# X2C_DC_SHIELD.net
KiCad netlist of a schematic drawn in EAGLE
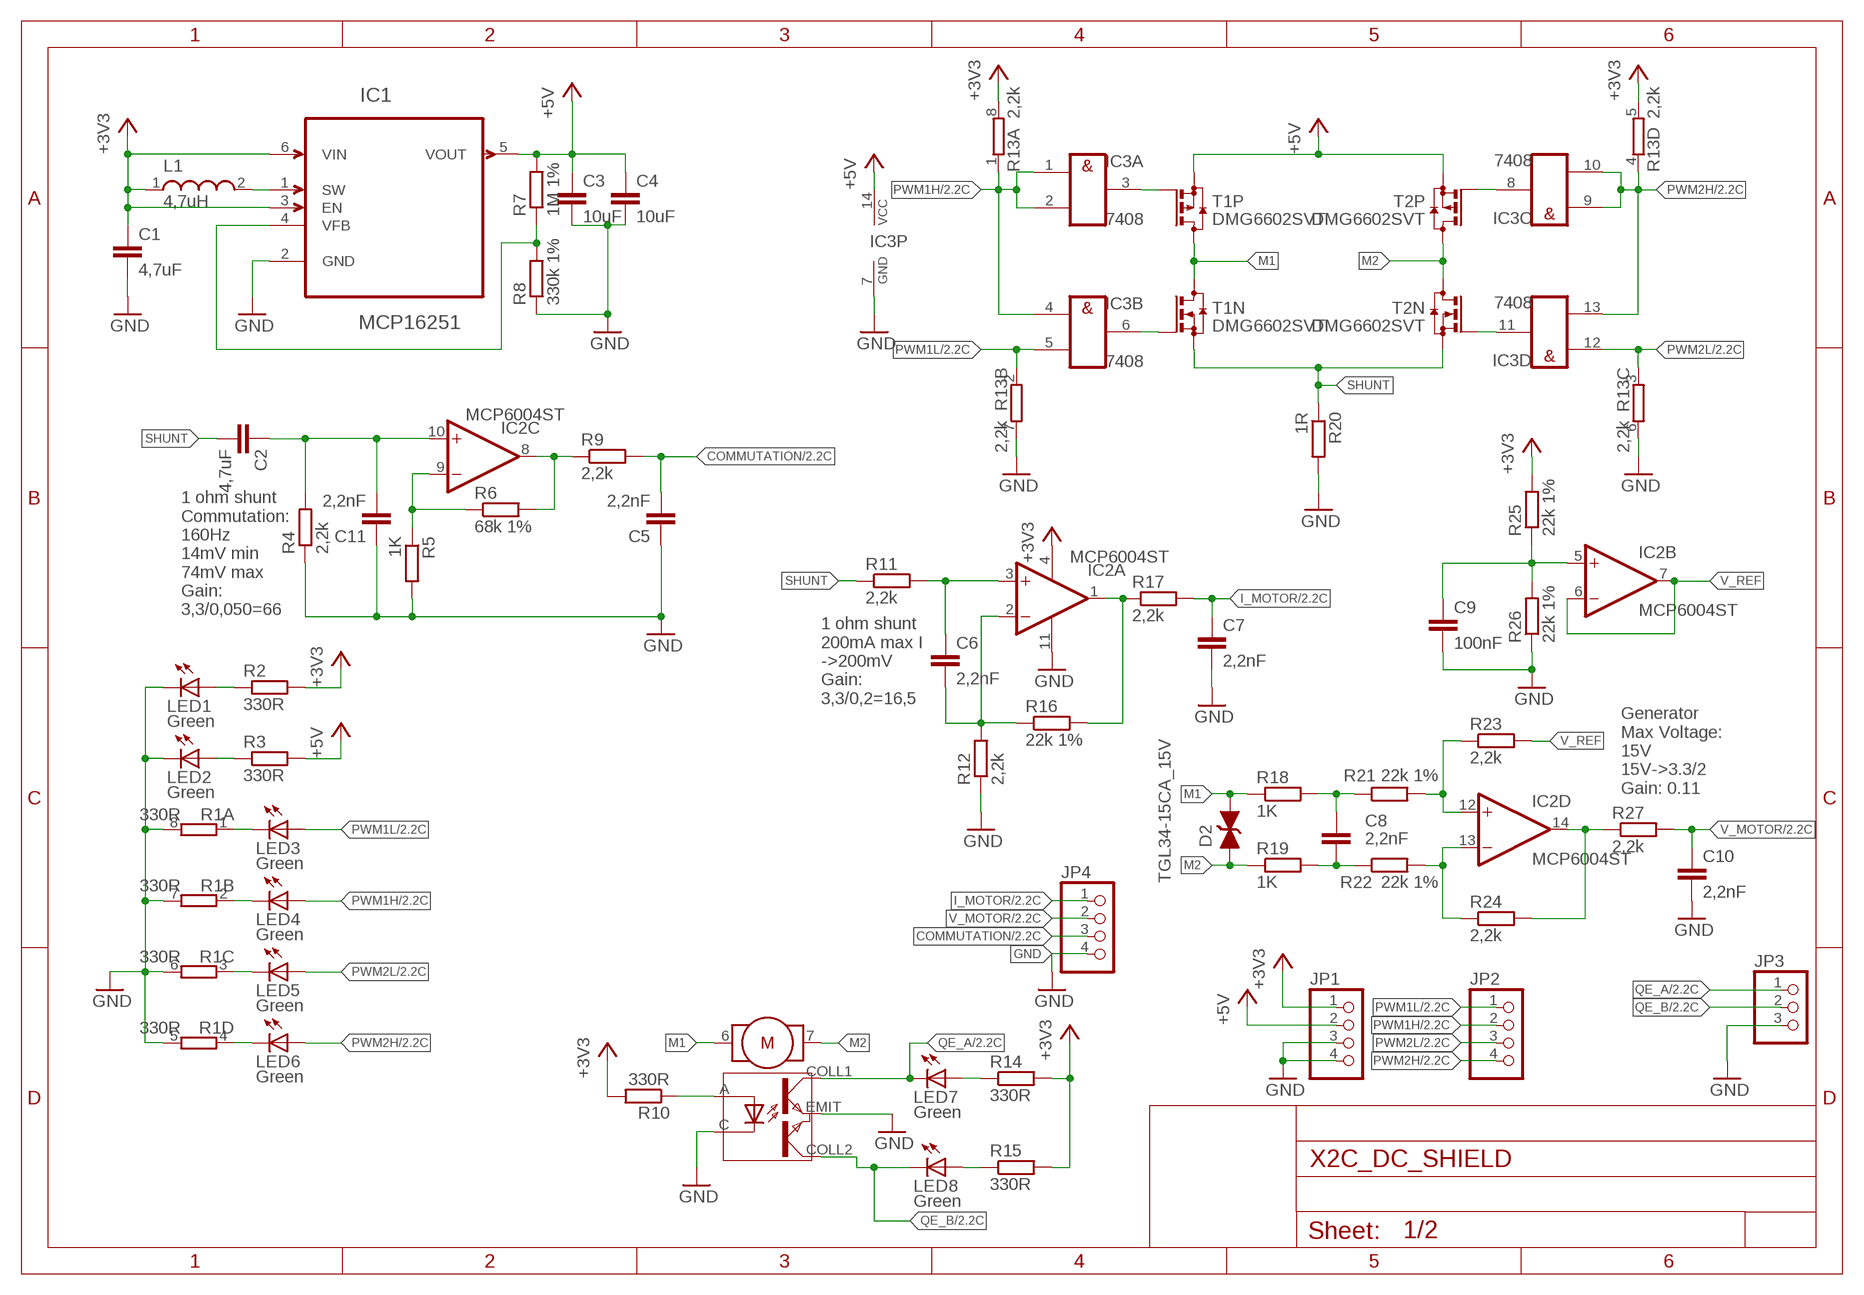
[diagram p0: schematic, sheet 1]
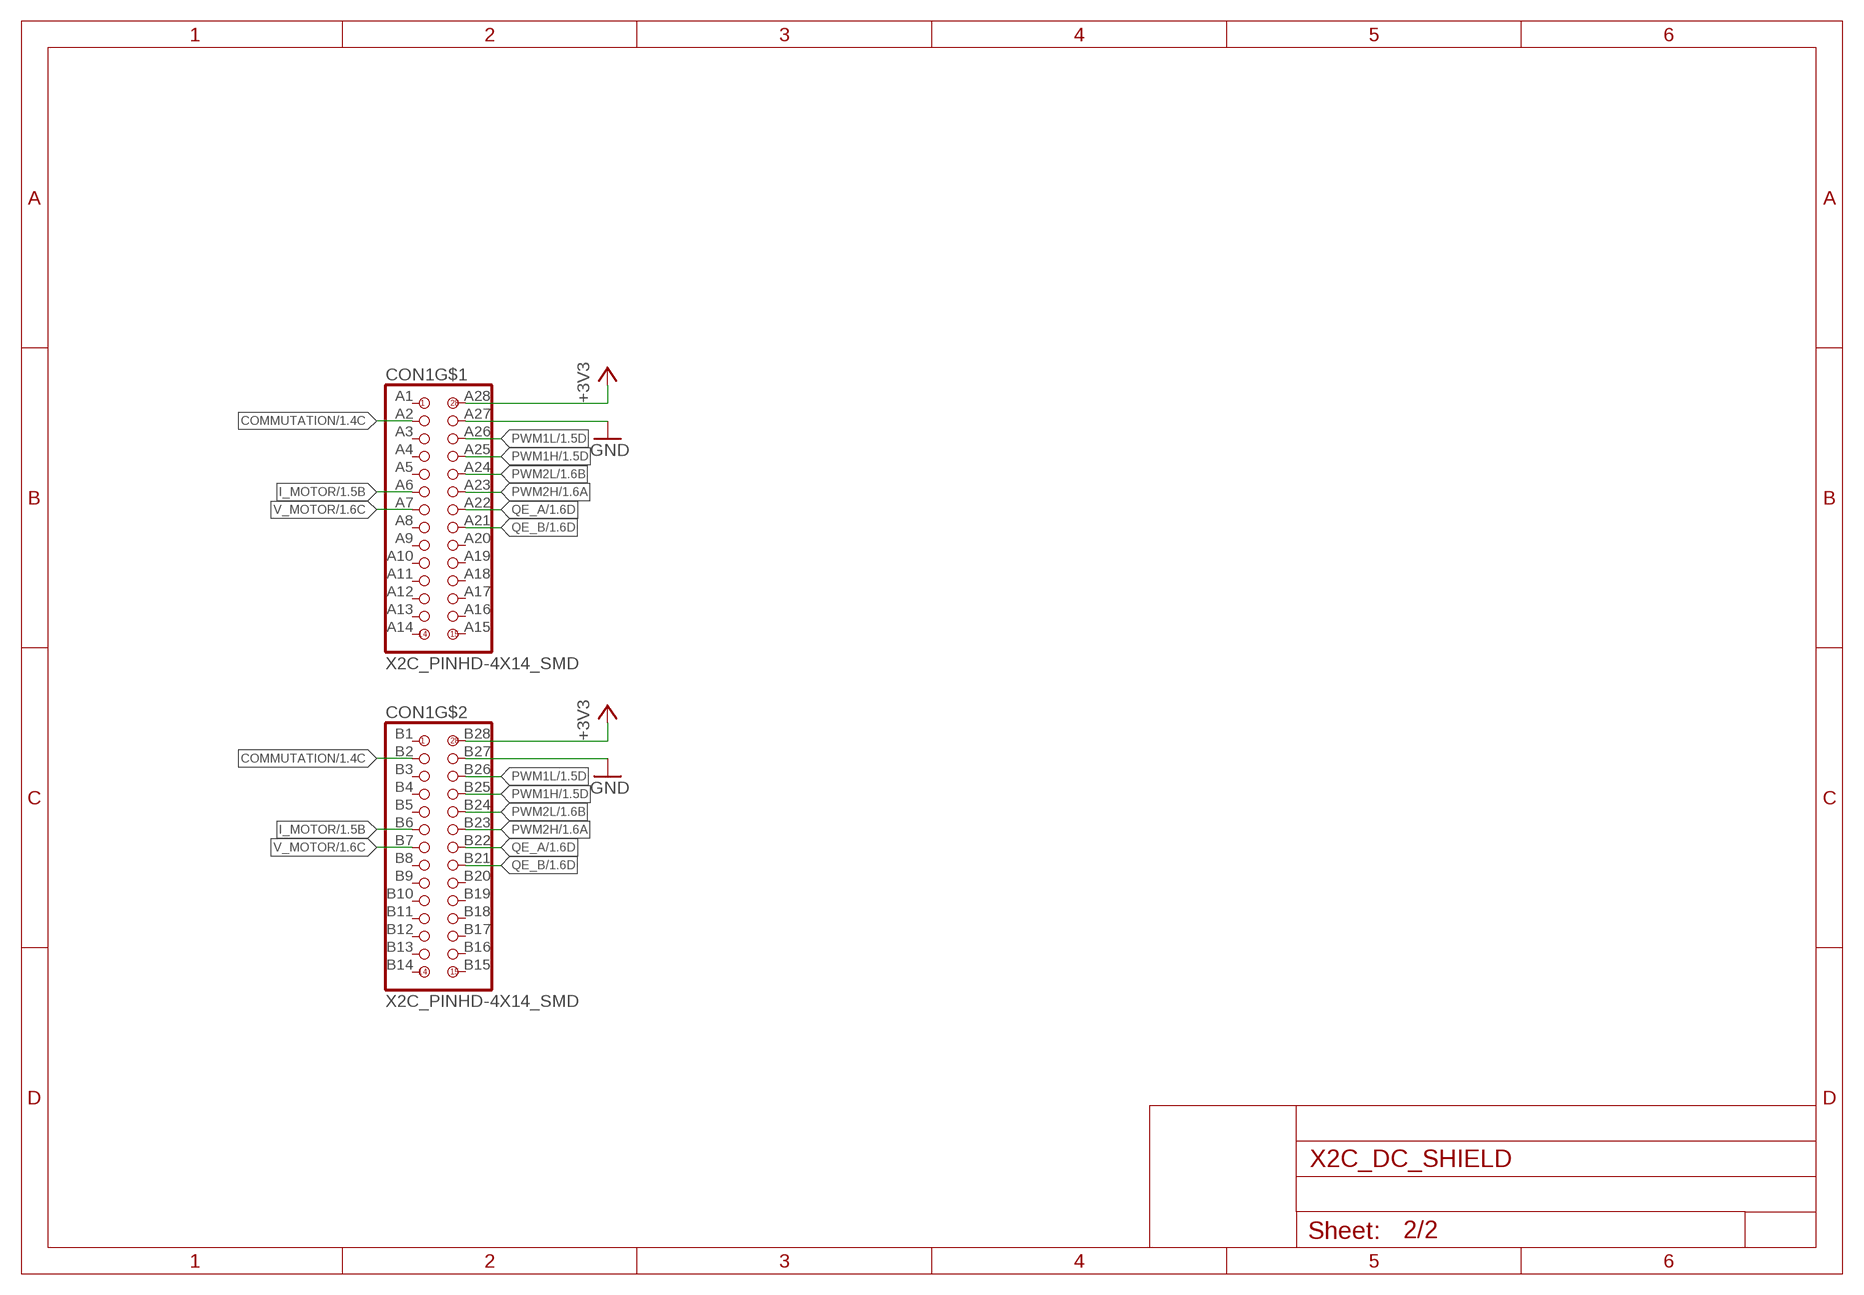
[diagram p1: schematic, sheet 2]

(export (version "E")
  (design (tool "Eeschema 10.0.6"))
  (components
    (comp (ref "CON1")
      (value "X2C_PINHD-4X14_SMD")
      (footprint "eagle-import:X2C_4X14_SMD")
      (libsource (lib "eagle-import") (part "X2C_PINHD-4X14_SMD"))
    )
    (comp (ref "C1")
      (value "4,7uF")
      (footprint "eagle-import:C0603K")
      (libsource (lib "eagle-import") (part "KANDO_KOZOS_C-EU-SMD_0603_4,7UF_16V"))
    )
    (comp (ref "C2")
      (value "4,7uF")
      (footprint "eagle-import:C0603K")
      (libsource (lib "eagle-import") (part "KANDO_KOZOS_C-EU-SMD_0603_4,7UF_16V"))
    )
    (comp (ref "C3")
      (value "10uF")
      (footprint "eagle-import:C0805K")
      (libsource (lib "eagle-import") (part "C-EU-SMD_0805_10UF_16V"))
    )
    (comp (ref "C4")
      (value "10uF")
      (footprint "eagle-import:C0805K")
      (libsource (lib "eagle-import") (part "C-EU-SMD_0805_10UF_16V"))
    )
    (comp (ref "C5")
      (value "2,2nF")
      (footprint "eagle-import:C0603K")
      (libsource (lib "eagle-import") (part "KANDO_KOZOS_C-EU-SMD_0603_2,2NF"))
    )
    (comp (ref "C6")
      (value "2,2nF")
      (footprint "eagle-import:C0603K")
      (libsource (lib "eagle-import") (part "KANDO_KOZOS_C-EU-SMD_0603_2,2NF"))
    )
    (comp (ref "C7")
      (value "2,2nF")
      (footprint "eagle-import:C0603K")
      (libsource (lib "eagle-import") (part "KANDO_KOZOS_C-EU-SMD_0603_2,2NF"))
    )
    (comp (ref "C8")
      (value "2,2nF")
      (footprint "eagle-import:C0603K")
      (libsource (lib "eagle-import") (part "KANDO_KOZOS_C-EU-SMD_0603_2,2NF"))
    )
    (comp (ref "C9")
      (value "100nF")
      (footprint "eagle-import:C0603K")
      (libsource (lib "eagle-import") (part "KANDO_KOZOS_C-EU-SMD_0603_100NF_50V"))
    )
    (comp (ref "C10")
      (value "2,2nF")
      (footprint "eagle-import:C0603K")
      (libsource (lib "eagle-import") (part "KANDO_KOZOS_C-EU-SMD_0603_2,2NF"))
    )
    (comp (ref "C11")
      (value "2,2nF")
      (footprint "eagle-import:C0603K")
      (libsource (lib "eagle-import") (part "KANDO_KOZOS_C-EU-SMD_0603_2,2NF"))
    )
    (comp (ref "D2")
      (value "TGL34-15CA_15V")
      (footprint "eagle-import:DO213AA")
      (libsource (lib "eagle-import") (part "TRANSIL_DUAL_DIODE"))
    )
    (comp (ref "IC1")
      (value "MCP16251")
      (footprint "eagle-import:SOT95P270X145-6N")
      (libsource (lib "eagle-import") (part "MCP16251"))
    )
    (comp (ref "IC2")
      (value "MCP6004ST")
      (footprint "eagle-import:TSSOP14")
      (libsource (lib "eagle-import") (part "MCP6004ST"))
    )
    (comp (ref "IC3")
      (value "7408")
      (footprint "eagle-import:TSSOP14")
      (libsource (lib "eagle-import") (part "7408"))
    )
    (comp (ref "JP1")
      (value "PINHD-1X4")
      (footprint "eagle-import:1X04")
      (libsource (lib "eagle-import") (part "PINHD-1X4"))
    )
    (comp (ref "JP2")
      (value "PINHD-1X4")
      (footprint "eagle-import:1X04")
      (libsource (lib "eagle-import") (part "PINHD-1X4"))
    )
    (comp (ref "JP3")
      (value "PINHD-1X03_2.54")
      (footprint "eagle-import:1X03")
      (libsource (lib "eagle-import") (part "PINHD-1X03_2.54"))
    )
    (comp (ref "JP4")
      (value "PINHD-1X4")
      (footprint "eagle-import:1X04")
      (libsource (lib "eagle-import") (part "PINHD-1X4"))
    )
    (comp (ref "L1")
      (value "4,7uH")
      (footprint "eagle-import:WE-TPC_3816")
      (libsource (lib "eagle-import") (part "WE-TPC_3816_4,7UH_0,9A"))
    )
    (comp (ref "LED1")
      (value "Green")
      (footprint "eagle-import:CHIPLED_0805")
      (libsource (lib "eagle-import") (part "LEDCHIPLED_0805_GREEN"))
    )
    (comp (ref "LED2")
      (value "Green")
      (footprint "eagle-import:CHIPLED_0805")
      (libsource (lib "eagle-import") (part "LEDCHIPLED_0805_GREEN"))
    )
    (comp (ref "LED3")
      (value "Green")
      (footprint "eagle-import:CHIPLED_0805")
      (libsource (lib "eagle-import") (part "LEDCHIPLED_0805_GREEN"))
    )
    (comp (ref "LED4")
      (value "Green")
      (footprint "eagle-import:CHIPLED_0805")
      (libsource (lib "eagle-import") (part "LEDCHIPLED_0805_GREEN"))
    )
    (comp (ref "LED5")
      (value "Green")
      (footprint "eagle-import:CHIPLED_0805")
      (libsource (lib "eagle-import") (part "LEDCHIPLED_0805_GREEN"))
    )
    (comp (ref "LED6")
      (value "Green")
      (footprint "eagle-import:CHIPLED_0805")
      (libsource (lib "eagle-import") (part "LEDCHIPLED_0805_GREEN"))
    )
    (comp (ref "LED7")
      (value "Green")
      (footprint "eagle-import:CHIPLED_0805")
      (libsource (lib "eagle-import") (part "LEDCHIPLED_0805_GREEN"))
    )
    (comp (ref "LED8")
      (value "Green")
      (footprint "eagle-import:CHIPLED_0805")
      (libsource (lib "eagle-import") (part "LEDCHIPLED_0805_GREEN"))
    )
    (comp (ref "MOT1")
      (value "DC_MOT")
      (footprint "eagle-import:DC_MOTOR")
      (libsource (lib "eagle-import") (part "DC_MOTOR_1"))
    )
    (comp (ref "R1")
      (value "330R")
      (footprint "eagle-import:EXBV8V_A")
      (libsource (lib "eagle-import") (part "4R-N330R"))
    )
    (comp (ref "R2")
      (value "330R")
      (footprint "eagle-import:R0603")
      (libsource (lib "eagle-import") (part "R-EU_SMDR0603_330R"))
    )
    (comp (ref "R3")
      (value "330R")
      (footprint "eagle-import:R0603")
      (libsource (lib "eagle-import") (part "R-EU_SMDR0603_330R"))
    )
    (comp (ref "R4")
      (value "2,2k")
      (footprint "eagle-import:R0603")
      (libsource (lib "eagle-import") (part "R-EU_SMDR0603_2,2K"))
    )
    (comp (ref "R5")
      (value "1K")
      (footprint "eagle-import:R0603")
      (libsource (lib "eagle-import") (part "R-EU_SMDR0603_1K_1%"))
    )
    (comp (ref "R6")
      (value "68k 1%")
      (footprint "eagle-import:R0603")
      (libsource (lib "eagle-import") (part "R-EU_SMDR0603_68K_1%"))
    )
    (comp (ref "R7")
      (value "1M 1%")
      (footprint "eagle-import:R0603")
      (libsource (lib "eagle-import") (part "R-EU_SMDR0603_1M_1%"))
    )
    (comp (ref "R8")
      (value "330k 1%")
      (footprint "eagle-import:R0603")
      (libsource (lib "eagle-import") (part "R-EU_SMDR0603_330K_1%"))
    )
    (comp (ref "R9")
      (value "2,2k")
      (footprint "eagle-import:R0603")
      (libsource (lib "eagle-import") (part "R-EU_SMDR0603_2,2K"))
    )
    (comp (ref "R10")
      (value "330R")
      (footprint "eagle-import:R0603")
      (libsource (lib "eagle-import") (part "R-EU_SMDR0603_330R"))
    )
    (comp (ref "R11")
      (value "2,2k")
      (footprint "eagle-import:R0603")
      (libsource (lib "eagle-import") (part "R-EU_SMDR0603_2,2K"))
    )
    (comp (ref "R12")
      (value "2,2k")
      (footprint "eagle-import:R0603")
      (libsource (lib "eagle-import") (part "R-EU_SMDR0603_2,2K"))
    )
    (comp (ref "R13")
      (value "2,2k")
      (footprint "eagle-import:EXBV8V_A")
      (libsource (lib "eagle-import") (part "4R-N2,2K"))
    )
    (comp (ref "R14")
      (value "330R")
      (footprint "eagle-import:R0603")
      (libsource (lib "eagle-import") (part "R-EU_SMDR0603_330R"))
    )
    (comp (ref "R15")
      (value "330R")
      (footprint "eagle-import:R0603")
      (libsource (lib "eagle-import") (part "R-EU_SMDR0603_330R"))
    )
    (comp (ref "R16")
      (value "22k 1%")
      (footprint "eagle-import:R0603")
      (libsource (lib "eagle-import") (part "R-EU_SMDR0603_22K_1%"))
    )
    (comp (ref "R17")
      (value "2,2k")
      (footprint "eagle-import:R0603")
      (libsource (lib "eagle-import") (part "R-EU_SMDR0603_2,2K"))
    )
    (comp (ref "R18")
      (value "1K")
      (footprint "eagle-import:R0603")
      (libsource (lib "eagle-import") (part "R-EU_SMDR0603_1K_1%"))
    )
    (comp (ref "R19")
      (value "1K")
      (footprint "eagle-import:R0603")
      (libsource (lib "eagle-import") (part "R-EU_SMDR0603_1K_1%"))
    )
    (comp (ref "R20")
      (value "1R")
      (footprint "eagle-import:R0805")
      (libsource (lib "eagle-import") (part "R-EU_SMDR0805_1R_1%"))
    )
    (comp (ref "R21")
      (value "22k 1%")
      (footprint "eagle-import:R0603")
      (libsource (lib "eagle-import") (part "R-EU_SMDR0603_22K_1%"))
    )
    (comp (ref "R22")
      (value "22k 1%")
      (footprint "eagle-import:R0603")
      (libsource (lib "eagle-import") (part "R-EU_SMDR0603_22K_1%"))
    )
    (comp (ref "R23")
      (value "2,2k")
      (footprint "eagle-import:R0603")
      (libsource (lib "eagle-import") (part "R-EU_SMDR0603_2,2K"))
    )
    (comp (ref "R24")
      (value "2,2k")
      (footprint "eagle-import:R0603")
      (libsource (lib "eagle-import") (part "R-EU_SMDR0603_2,2K"))
    )
    (comp (ref "R25")
      (value "22k 1%")
      (footprint "eagle-import:R0603")
      (libsource (lib "eagle-import") (part "R-EU_SMDR0603_22K_1%"))
    )
    (comp (ref "R26")
      (value "22k 1%")
      (footprint "eagle-import:R0603")
      (libsource (lib "eagle-import") (part "R-EU_SMDR0603_22K_1%"))
    )
    (comp (ref "R27")
      (value "2,2k")
      (footprint "eagle-import:R0603")
      (libsource (lib "eagle-import") (part "R-EU_SMDR0603_2,2K"))
    )
    (comp (ref "T1")
      (value "DMG6602SVT")
      (footprint "eagle-import:TSOT23-6")
      (libsource (lib "eagle-import") (part "DMG6602SVT"))
    )
    (comp (ref "T2")
      (value "DMG6602SVT")
      (footprint "eagle-import:TSOT23-6")
      (libsource (lib "eagle-import") (part "DMG6602SVT"))
    )
  )
  (nets
    (net (code "1") (name "+3V3") (class "Default")
      (node (ref "C1") (pin "1") (pinfunction "1_1") (pintype "passive"))
      (node (ref "CON1") (pin "A28") (pinfunction "A28_A28") (pintype "passive"))
      (node (ref "CON1") (pin "B28") (pinfunction "A28_B28") (pintype "passive"))
      (node (ref "IC1") (pin "3") (pinfunction "EN_3") (pintype "input"))
      (node (ref "IC1") (pin "6") (pinfunction "VIN_6") (pintype "input"))
      (node (ref "IC2") (pin "4") (pinfunction "V+_4") (pintype "power_in"))
      (node (ref "JP1") (pin "1") (pinfunction "1_1") (pintype "passive"))
      (node (ref "L1") (pin "1") (pinfunction "1_1") (pintype "passive"))
      (node (ref "R10") (pin "2") (pinfunction "2_2") (pintype "passive"))
      (node (ref "R13") (pin "5") (pinfunction "2_5") (pintype "passive"))
      (node (ref "R13") (pin "8") (pinfunction "2_8") (pintype "passive"))
      (node (ref "R14") (pin "2") (pinfunction "2_2") (pintype "passive"))
      (node (ref "R15") (pin "2") (pinfunction "2_2") (pintype "passive"))
      (node (ref "R2") (pin "2") (pinfunction "2_2") (pintype "passive"))
      (node (ref "R25") (pin "2") (pinfunction "2_2") (pintype "passive"))
    )
    (net (code "2") (name "+5V") (class "Default")
      (node (ref "C3") (pin "1") (pinfunction "1_1") (pintype "passive"))
      (node (ref "C4") (pin "1") (pinfunction "1_1") (pintype "passive"))
      (node (ref "IC1") (pin "5") (pinfunction "VOUT_5") (pintype "output"))
      (node (ref "IC3") (pin "14") (pinfunction "VCC_14") (pintype "power_in"))
      (node (ref "JP1") (pin "2") (pinfunction "2_2") (pintype "passive"))
      (node (ref "R3") (pin "2") (pinfunction "2_2") (pintype "passive"))
      (node (ref "R7") (pin "2") (pinfunction "2_2") (pintype "passive"))
      (node (ref "T1") (pin "2") (pinfunction "S_2") (pintype "passive"))
      (node (ref "T2") (pin "2") (pinfunction "S_2") (pintype "passive"))
    )
    (net (code "3") (name "COMMUTATION") (class "Default")
      (node (ref "C5") (pin "2") (pinfunction "2_2") (pintype "passive"))
      (node (ref "CON1") (pin "A2") (pinfunction "A2_A2") (pintype "passive"))
      (node (ref "CON1") (pin "B2") (pinfunction "A2_B2") (pintype "passive"))
      (node (ref "JP4") (pin "3") (pinfunction "3_3") (pintype "passive"))
      (node (ref "R9") (pin "2") (pinfunction "2_2") (pintype "passive"))
    )
    (net (code "4") (name "GND") (class "Default")
      (node (ref "C1") (pin "2") (pinfunction "2_2") (pintype "passive"))
      (node (ref "C10") (pin "2") (pinfunction "2_2") (pintype "passive"))
      (node (ref "C11") (pin "1") (pinfunction "1_1") (pintype "passive"))
      (node (ref "C3") (pin "2") (pinfunction "2_2") (pintype "passive"))
      (node (ref "C4") (pin "2") (pinfunction "2_2") (pintype "passive"))
      (node (ref "C5") (pin "1") (pinfunction "1_1") (pintype "passive"))
      (node (ref "C7") (pin "2") (pinfunction "2_2") (pintype "passive"))
      (node (ref "C9") (pin "2") (pinfunction "2_2") (pintype "passive"))
      (node (ref "CON1") (pin "A27") (pinfunction "A27_A27") (pintype "passive"))
      (node (ref "CON1") (pin "B27") (pinfunction "A27_B27") (pintype "passive"))
      (node (ref "IC1") (pin "2") (pinfunction "GND_2") (pintype "passive"))
      (node (ref "IC2") (pin "11") (pinfunction "V-_11") (pintype "power_in"))
      (node (ref "IC3") (pin "7") (pinfunction "GND_7") (pintype "power_in"))
      (node (ref "JP1") (pin "3") (pinfunction "3_3") (pintype "passive"))
      (node (ref "JP1") (pin "4") (pinfunction "4_4") (pintype "passive"))
      (node (ref "JP3") (pin "3") (pinfunction "3_3") (pintype "passive"))
      (node (ref "JP4") (pin "4") (pinfunction "4_4") (pintype "passive"))
      (node (ref "LED1") (pin "C") (pinfunction "C_C") (pintype "passive"))
      (node (ref "LED2") (pin "C") (pinfunction "C_C") (pintype "passive"))
      (node (ref "MOT1") (pin "C") (pinfunction "C_C") (pintype "passive"))
      (node (ref "MOT1") (pin "EMIT") (pinfunction "EMIT_EMIT") (pintype "passive"))
      (node (ref "R1") (pin "5") (pinfunction "2_5") (pintype "passive"))
      (node (ref "R1") (pin "6") (pinfunction "2_6") (pintype "passive"))
      (node (ref "R1") (pin "7") (pinfunction "2_7") (pintype "passive"))
      (node (ref "R1") (pin "8") (pinfunction "2_8") (pintype "passive"))
      (node (ref "R12") (pin "1") (pinfunction "1_1") (pintype "passive"))
      (node (ref "R13") (pin "6") (pinfunction "2_6") (pintype "passive"))
      (node (ref "R13") (pin "7") (pinfunction "2_7") (pintype "passive"))
      (node (ref "R20") (pin "2") (pinfunction "2_2") (pintype "passive"))
      (node (ref "R26") (pin "1") (pinfunction "1_1") (pintype "passive"))
      (node (ref "R4") (pin "1") (pinfunction "1_1") (pintype "passive"))
      (node (ref "R5") (pin "2") (pinfunction "2_2") (pintype "passive"))
      (node (ref "R8") (pin "1") (pinfunction "1_1") (pintype "passive"))
    )
    (net (code "5") (name "I_MOTOR") (class "Default")
      (node (ref "C7") (pin "1") (pinfunction "1_1") (pintype "passive"))
      (node (ref "CON1") (pin "A6") (pinfunction "A6_A6") (pintype "passive"))
      (node (ref "CON1") (pin "B6") (pinfunction "A6_B6") (pintype "passive"))
      (node (ref "JP4") (pin "1") (pinfunction "1_1") (pintype "passive"))
      (node (ref "R17") (pin "2") (pinfunction "2_2") (pintype "passive"))
    )
    (net (code "6") (name "M1") (class "Default")
      (node (ref "D2") (pin "C") (pinfunction "P$2_C") (pintype "bidirectional"))
      (node (ref "MOT1") (pin "6") (pinfunction "MOT1_6") (pintype "passive"))
      (node (ref "R18") (pin "1") (pinfunction "1_1") (pintype "passive"))
      (node (ref "T1") (pin "4") (pinfunction "D_4") (pintype "passive"))
      (node (ref "T1") (pin "6") (pinfunction "D_6") (pintype "passive"))
    )
    (net (code "7") (name "M2") (class "Default")
      (node (ref "D2") (pin "A") (pinfunction "P$1_A") (pintype "bidirectional"))
      (node (ref "MOT1") (pin "7") (pinfunction "MOT2_7") (pintype "passive"))
      (node (ref "R19") (pin "1") (pinfunction "1_1") (pintype "passive"))
      (node (ref "T2") (pin "4") (pinfunction "D_4") (pintype "passive"))
      (node (ref "T2") (pin "6") (pinfunction "D_6") (pintype "passive"))
    )
    (net (code "8") (name "Net-(C8-Pad1)") (class "Default")
      (node (ref "C8") (pin "1") (pinfunction "1_1") (pintype "passive"))
      (node (ref "R18") (pin "2") (pinfunction "2_2") (pintype "passive"))
      (node (ref "R21") (pin "1") (pinfunction "1_1") (pintype "passive"))
    )
    (net (code "9") (name "Net-(C8-Pad2)") (class "Default")
      (node (ref "C8") (pin "2") (pinfunction "2_2") (pintype "passive"))
      (node (ref "R19") (pin "2") (pinfunction "2_2") (pintype "passive"))
      (node (ref "R22") (pin "1") (pinfunction "1_1") (pintype "passive"))
    )
    (net (code "10") (name "Net-(IC1-SW)") (class "Default")
      (node (ref "IC1") (pin "1") (pinfunction "SW_1") (pintype "input"))
      (node (ref "L1") (pin "2") (pinfunction "2_2") (pintype "passive"))
    )
    (net (code "11") (name "Net-(IC1-VFB)") (class "Default")
      (node (ref "IC1") (pin "4") (pinfunction "VFB_4") (pintype "input"))
      (node (ref "R7") (pin "1") (pinfunction "1_1") (pintype "passive"))
      (node (ref "R8") (pin "2") (pinfunction "2_2") (pintype "passive"))
    )
    (net (code "12") (name "Net-(IC2A-+IN)") (class "Default")
      (node (ref "C6") (pin "1") (pinfunction "1_1") (pintype "passive"))
      (node (ref "IC2") (pin "3") (pinfunction "+IN_3") (pintype "input"))
      (node (ref "R11") (pin "2") (pinfunction "2_2") (pintype "passive"))
    )
    (net (code "13") (name "Net-(IC2A--IN)") (class "Default")
      (node (ref "C6") (pin "2") (pinfunction "2_2") (pintype "passive"))
      (node (ref "IC2") (pin "2") (pinfunction "-IN_2") (pintype "input"))
      (node (ref "R12") (pin "2") (pinfunction "2_2") (pintype "passive"))
      (node (ref "R16") (pin "1") (pinfunction "1_1") (pintype "passive"))
    )
    (net (code "14") (name "Net-(IC2A-OUT)") (class "Default")
      (node (ref "IC2") (pin "1") (pinfunction "OUT_1") (pintype "output"))
      (node (ref "R16") (pin "2") (pinfunction "2_2") (pintype "passive"))
      (node (ref "R17") (pin "1") (pinfunction "1_1") (pintype "passive"))
    )
    (net (code "15") (name "Net-(IC2B-+IN)") (class "Default")
      (node (ref "C9") (pin "1") (pinfunction "1_1") (pintype "passive"))
      (node (ref "IC2") (pin "5") (pinfunction "+IN_5") (pintype "input"))
      (node (ref "R25") (pin "1") (pinfunction "1_1") (pintype "passive"))
      (node (ref "R26") (pin "2") (pinfunction "2_2") (pintype "passive"))
    )
    (net (code "16") (name "Net-(IC2C-+IN)") (class "Default")
      (node (ref "C11") (pin "2") (pinfunction "2_2") (pintype "passive"))
      (node (ref "C2") (pin "1") (pinfunction "1_1") (pintype "passive"))
      (node (ref "IC2") (pin "10") (pinfunction "+IN_10") (pintype "input"))
      (node (ref "R4") (pin "2") (pinfunction "2_2") (pintype "passive"))
    )
    (net (code "17") (name "Net-(IC2C--IN)") (class "Default")
      (node (ref "IC2") (pin "9") (pinfunction "-IN_9") (pintype "input"))
      (node (ref "R5") (pin "1") (pinfunction "1_1") (pintype "passive"))
      (node (ref "R6") (pin "1") (pinfunction "1_1") (pintype "passive"))
    )
    (net (code "18") (name "Net-(IC2C-OUT)") (class "Default")
      (node (ref "IC2") (pin "8") (pinfunction "OUT_8") (pintype "output"))
      (node (ref "R6") (pin "2") (pinfunction "2_2") (pintype "passive"))
      (node (ref "R9") (pin "1") (pinfunction "1_1") (pintype "passive"))
    )
    (net (code "19") (name "Net-(IC2D-+IN)") (class "Default")
      (node (ref "IC2") (pin "12") (pinfunction "+IN_12") (pintype "input"))
      (node (ref "R21") (pin "2") (pinfunction "2_2") (pintype "passive"))
      (node (ref "R23") (pin "1") (pinfunction "1_1") (pintype "passive"))
    )
    (net (code "20") (name "Net-(IC2D--IN)") (class "Default")
      (node (ref "IC2") (pin "13") (pinfunction "-IN_13") (pintype "input"))
      (node (ref "R22") (pin "2") (pinfunction "2_2") (pintype "passive"))
      (node (ref "R24") (pin "1") (pinfunction "1_1") (pintype "passive"))
    )
    (net (code "21") (name "Net-(IC2D-OUT)") (class "Default")
      (node (ref "IC2") (pin "14") (pinfunction "OUT_14") (pintype "output"))
      (node (ref "R24") (pin "2") (pinfunction "2_2") (pintype "passive"))
      (node (ref "R27") (pin "1") (pinfunction "1_1") (pintype "passive"))
    )
    (net (code "22") (name "Net-(IC3A-O)") (class "Default")
      (node (ref "IC3") (pin "3") (pinfunction "O_3") (pintype "output"))
      (node (ref "T1") (pin "3") (pinfunction "G_3") (pintype "passive"))
    )
    (net (code "23") (name "Net-(IC3B-O)") (class "Default")
      (node (ref "IC3") (pin "6") (pinfunction "O_6") (pintype "output"))
      (node (ref "T1") (pin "1") (pinfunction "G_1") (pintype "passive"))
    )
    (net (code "24") (name "Net-(IC3C-O)") (class "Default")
      (node (ref "IC3") (pin "8") (pinfunction "O_8") (pintype "output"))
      (node (ref "T2") (pin "3") (pinfunction "G_3") (pintype "passive"))
    )
    (net (code "25") (name "Net-(IC3D-O)") (class "Default")
      (node (ref "IC3") (pin "11") (pinfunction "O_11") (pintype "output"))
      (node (ref "T2") (pin "1") (pinfunction "G_1") (pintype "passive"))
    )
    (net (code "26") (name "Net-(LED1-PadA)") (class "Default")
      (node (ref "LED1") (pin "A") (pinfunction "A_A") (pintype "passive"))
      (node (ref "R2") (pin "1") (pinfunction "1_1") (pintype "passive"))
    )
    (net (code "27") (name "Net-(LED2-PadA)") (class "Default")
      (node (ref "LED2") (pin "A") (pinfunction "A_A") (pintype "passive"))
      (node (ref "R3") (pin "1") (pinfunction "1_1") (pintype "passive"))
    )
    (net (code "28") (name "Net-(LED3-PadC)") (class "Default")
      (node (ref "LED3") (pin "C") (pinfunction "C_C") (pintype "passive"))
      (node (ref "R1") (pin "1") (pinfunction "1_1") (pintype "passive"))
    )
    (net (code "29") (name "Net-(LED7-PadA)") (class "Default")
      (node (ref "LED7") (pin "A") (pinfunction "A_A") (pintype "passive"))
      (node (ref "R14") (pin "1") (pinfunction "1_1") (pintype "passive"))
    )
    (net (code "30") (name "Net-(LED8-PadA)") (class "Default")
      (node (ref "LED8") (pin "A") (pinfunction "A_A") (pintype "passive"))
      (node (ref "R15") (pin "1") (pinfunction "1_1") (pintype "passive"))
    )
    (net (code "31") (name "Net-(MOT1-PadA)") (class "Default")
      (node (ref "MOT1") (pin "A") (pinfunction "A_A") (pintype "passive"))
      (node (ref "R10") (pin "1") (pinfunction "1_1") (pintype "passive"))
    )
    (net (code "32") (name "Net-(R1B-1)") (class "Default")
      (node (ref "LED4") (pin "C") (pinfunction "C_C") (pintype "passive"))
      (node (ref "R1") (pin "2") (pinfunction "1_2") (pintype "passive"))
    )
    (net (code "33") (name "Net-(R1C-1)") (class "Default")
      (node (ref "LED5") (pin "C") (pinfunction "C_C") (pintype "passive"))
      (node (ref "R1") (pin "3") (pinfunction "1_3") (pintype "passive"))
    )
    (net (code "34") (name "Net-(R1D-1)") (class "Default")
      (node (ref "LED6") (pin "C") (pinfunction "C_C") (pintype "passive"))
      (node (ref "R1") (pin "4") (pinfunction "1_4") (pintype "passive"))
    )
    (net (code "35") (name "PWM1H") (class "Default")
      (node (ref "CON1") (pin "A25") (pinfunction "A25_A25") (pintype "passive"))
      (node (ref "CON1") (pin "B25") (pinfunction "A25_B25") (pintype "passive"))
      (node (ref "IC3") (pin "1") (pinfunction "I0_1") (pintype "input"))
      (node (ref "IC3") (pin "2") (pinfunction "I1_2") (pintype "input"))
      (node (ref "IC3") (pin "4") (pinfunction "I0_4") (pintype "input"))
      (node (ref "JP2") (pin "2") (pinfunction "2_2") (pintype "passive"))
      (node (ref "LED4") (pin "A") (pinfunction "A_A") (pintype "passive"))
      (node (ref "R13") (pin "1") (pinfunction "1_1") (pintype "passive"))
    )
    (net (code "36") (name "PWM1L") (class "Default")
      (node (ref "CON1") (pin "A26") (pinfunction "A26_A26") (pintype "passive"))
      (node (ref "CON1") (pin "B26") (pinfunction "A26_B26") (pintype "passive"))
      (node (ref "IC3") (pin "5") (pinfunction "I1_5") (pintype "input"))
      (node (ref "JP2") (pin "1") (pinfunction "1_1") (pintype "passive"))
      (node (ref "LED3") (pin "A") (pinfunction "A_A") (pintype "passive"))
      (node (ref "R13") (pin "2") (pinfunction "1_2") (pintype "passive"))
    )
    (net (code "37") (name "PWM2H") (class "Default")
      (node (ref "CON1") (pin "A23") (pinfunction "A23_A23") (pintype "passive"))
      (node (ref "CON1") (pin "B23") (pinfunction "A23_B23") (pintype "passive"))
      (node (ref "IC3") (pin "10") (pinfunction "I1_10") (pintype "input"))
      (node (ref "IC3") (pin "13") (pinfunction "I1_13") (pintype "input"))
      (node (ref "IC3") (pin "9") (pinfunction "I0_9") (pintype "input"))
      (node (ref "JP2") (pin "4") (pinfunction "4_4") (pintype "passive"))
      (node (ref "LED6") (pin "A") (pinfunction "A_A") (pintype "passive"))
      (node (ref "R13") (pin "4") (pinfunction "1_4") (pintype "passive"))
    )
    (net (code "38") (name "PWM2L") (class "Default")
      (node (ref "CON1") (pin "A24") (pinfunction "A24_A24") (pintype "passive"))
      (node (ref "CON1") (pin "B24") (pinfunction "A24_B24") (pintype "passive"))
      (node (ref "IC3") (pin "12") (pinfunction "I0_12") (pintype "input"))
      (node (ref "JP2") (pin "3") (pinfunction "3_3") (pintype "passive"))
      (node (ref "LED5") (pin "A") (pinfunction "A_A") (pintype "passive"))
      (node (ref "R13") (pin "3") (pinfunction "1_3") (pintype "passive"))
    )
    (net (code "39") (name "QE_A") (class "Default")
      (node (ref "CON1") (pin "A22") (pinfunction "A22_A22") (pintype "passive"))
      (node (ref "CON1") (pin "B22") (pinfunction "A22_B22") (pintype "passive"))
      (node (ref "JP3") (pin "1") (pinfunction "1_1") (pintype "passive"))
      (node (ref "LED7") (pin "C") (pinfunction "C_C") (pintype "passive"))
      (node (ref "MOT1") (pin "COLL1") (pinfunction "COL1_COLL1") (pintype "passive"))
    )
    (net (code "40") (name "QE_B") (class "Default")
      (node (ref "CON1") (pin "A21") (pinfunction "A21_A21") (pintype "passive"))
      (node (ref "CON1") (pin "B21") (pinfunction "A21_B21") (pintype "passive"))
      (node (ref "JP3") (pin "2") (pinfunction "2_2") (pintype "passive"))
      (node (ref "LED8") (pin "C") (pinfunction "C_C") (pintype "passive"))
      (node (ref "MOT1") (pin "COLL2") (pinfunction "COL2_COLL2") (pintype "passive"))
    )
    (net (code "41") (name "SHUNT") (class "Default")
      (node (ref "C2") (pin "2") (pinfunction "2_2") (pintype "passive"))
      (node (ref "R11") (pin "1") (pinfunction "1_1") (pintype "passive"))
      (node (ref "R20") (pin "1") (pinfunction "1_1") (pintype "passive"))
      (node (ref "T1") (pin "5") (pinfunction "S_5") (pintype "passive"))
      (node (ref "T2") (pin "5") (pinfunction "S_5") (pintype "passive"))
    )
    (net (code "42") (name "V_MOTOR") (class "Default")
      (node (ref "C10") (pin "1") (pinfunction "1_1") (pintype "passive"))
      (node (ref "CON1") (pin "A7") (pinfunction "A7_A7") (pintype "passive"))
      (node (ref "CON1") (pin "B7") (pinfunction "A7_B7") (pintype "passive"))
      (node (ref "JP4") (pin "2") (pinfunction "2_2") (pintype "passive"))
      (node (ref "R27") (pin "2") (pinfunction "2_2") (pintype "passive"))
    )
    (net (code "43") (name "V_REF") (class "Default")
      (node (ref "IC2") (pin "6") (pinfunction "-IN_6") (pintype "input"))
      (node (ref "IC2") (pin "7") (pinfunction "OUT_7") (pintype "output"))
      (node (ref "R23") (pin "2") (pinfunction "2_2") (pintype "passive"))
    )
    (net (code "44") (name "unconnected-(CON1-PadA1)") (class "Default")
      (node (ref "CON1") (pin "A1") (pinfunction "A1_A1") (pintype "passive"))
    )
    (net (code "45") (name "unconnected-(CON1-PadA3)") (class "Default")
      (node (ref "CON1") (pin "A3") (pinfunction "A3_A3") (pintype "passive"))
    )
    (net (code "46") (name "unconnected-(CON1-PadA4)") (class "Default")
      (node (ref "CON1") (pin "A4") (pinfunction "A4_A4") (pintype "passive"))
    )
    (net (code "47") (name "unconnected-(CON1-PadA5)") (class "Default")
      (node (ref "CON1") (pin "A5") (pinfunction "A5_A5") (pintype "passive"))
    )
    (net (code "48") (name "unconnected-(CON1-PadA8)") (class "Default")
      (node (ref "CON1") (pin "A8") (pinfunction "A8_A8") (pintype "passive"))
    )
    (net (code "49") (name "unconnected-(CON1-PadA9)") (class "Default")
      (node (ref "CON1") (pin "A9") (pinfunction "A9_A9") (pintype "passive"))
    )
    (net (code "50") (name "unconnected-(CON1-PadA10)") (class "Default")
      (node (ref "CON1") (pin "A10") (pinfunction "A10_A10") (pintype "passive"))
    )
    (net (code "51") (name "unconnected-(CON1-PadA11)") (class "Default")
      (node (ref "CON1") (pin "A11") (pinfunction "A11_A11") (pintype "passive"))
    )
    (net (code "52") (name "unconnected-(CON1-PadA12)") (class "Default")
      (node (ref "CON1") (pin "A12") (pinfunction "A12_A12") (pintype "passive"))
    )
    (net (code "53") (name "unconnected-(CON1-PadA13)") (class "Default")
      (node (ref "CON1") (pin "A13") (pinfunction "A13_A13") (pintype "passive"))
    )
    (net (code "54") (name "unconnected-(CON1-PadA14)") (class "Default")
      (node (ref "CON1") (pin "A14") (pinfunction "A14_A14") (pintype "passive"))
    )
    (net (code "55") (name "unconnected-(CON1-PadA15)") (class "Default")
      (node (ref "CON1") (pin "A15") (pinfunction "A15_A15") (pintype "passive"))
    )
    (net (code "56") (name "unconnected-(CON1-PadA16)") (class "Default")
      (node (ref "CON1") (pin "A16") (pinfunction "A16_A16") (pintype "passive"))
    )
    (net (code "57") (name "unconnected-(CON1-PadA17)") (class "Default")
      (node (ref "CON1") (pin "A17") (pinfunction "A17_A17") (pintype "passive"))
    )
    (net (code "58") (name "unconnected-(CON1-PadA18)") (class "Default")
      (node (ref "CON1") (pin "A18") (pinfunction "A18_A18") (pintype "passive"))
    )
    (net (code "59") (name "unconnected-(CON1-PadA19)") (class "Default")
      (node (ref "CON1") (pin "A19") (pinfunction "A19_A19") (pintype "passive"))
    )
    (net (code "60") (name "unconnected-(CON1-PadA20)") (class "Default")
      (node (ref "CON1") (pin "A20") (pinfunction "A20_A20") (pintype "passive"))
    )
    (net (code "61") (name "unconnected-(CON1B-A1-PadB1)") (class "Default")
      (node (ref "CON1") (pin "B1") (pinfunction "A1_B1") (pintype "passive"))
    )
    (net (code "62") (name "unconnected-(CON1B-A3-PadB3)") (class "Default")
      (node (ref "CON1") (pin "B3") (pinfunction "A3_B3") (pintype "passive"))
    )
    (net (code "63") (name "unconnected-(CON1B-A4-PadB4)") (class "Default")
      (node (ref "CON1") (pin "B4") (pinfunction "A4_B4") (pintype "passive"))
    )
    (net (code "64") (name "unconnected-(CON1B-A5-PadB5)") (class "Default")
      (node (ref "CON1") (pin "B5") (pinfunction "A5_B5") (pintype "passive"))
    )
    (net (code "65") (name "unconnected-(CON1B-A8-PadB8)") (class "Default")
      (node (ref "CON1") (pin "B8") (pinfunction "A8_B8") (pintype "passive"))
    )
    (net (code "66") (name "unconnected-(CON1B-A9-PadB9)") (class "Default")
      (node (ref "CON1") (pin "B9") (pinfunction "A9_B9") (pintype "passive"))
    )
    (net (code "67") (name "unconnected-(CON1B-A10-PadB10)") (class "Default")
      (node (ref "CON1") (pin "B10") (pinfunction "A10_B10") (pintype "passive"))
    )
    (net (code "68") (name "unconnected-(CON1B-A11-PadB11)") (class "Default")
      (node (ref "CON1") (pin "B11") (pinfunction "A11_B11") (pintype "passive"))
    )
    (net (code "69") (name "unconnected-(CON1B-A12-PadB12)") (class "Default")
      (node (ref "CON1") (pin "B12") (pinfunction "A12_B12") (pintype "passive"))
    )
    (net (code "70") (name "unconnected-(CON1B-A13-PadB13)") (class "Default")
      (node (ref "CON1") (pin "B13") (pinfunction "A13_B13") (pintype "passive"))
    )
    (net (code "71") (name "unconnected-(CON1B-A14-PadB14)") (class "Default")
      (node (ref "CON1") (pin "B14") (pinfunction "A14_B14") (pintype "passive"))
    )
    (net (code "72") (name "unconnected-(CON1B-A15-PadB15)") (class "Default")
      (node (ref "CON1") (pin "B15") (pinfunction "A15_B15") (pintype "passive"))
    )
    (net (code "73") (name "unconnected-(CON1B-A16-PadB16)") (class "Default")
      (node (ref "CON1") (pin "B16") (pinfunction "A16_B16") (pintype "passive"))
    )
    (net (code "74") (name "unconnected-(CON1B-A17-PadB17)") (class "Default")
      (node (ref "CON1") (pin "B17") (pinfunction "A17_B17") (pintype "passive"))
    )
    (net (code "75") (name "unconnected-(CON1B-A18-PadB18)") (class "Default")
      (node (ref "CON1") (pin "B18") (pinfunction "A18_B18") (pintype "passive"))
    )
    (net (code "76") (name "unconnected-(CON1B-A19-PadB19)") (class "Default")
      (node (ref "CON1") (pin "B19") (pinfunction "A19_B19") (pintype "passive"))
    )
    (net (code "77") (name "unconnected-(CON1B-A20-PadB20)") (class "Default")
      (node (ref "CON1") (pin "B20") (pinfunction "A20_B20") (pintype "passive"))
    )
  )
)
